# CW308T_EMF32TG11.net
KiCad netlist of a schematic drawn in Altium Designer
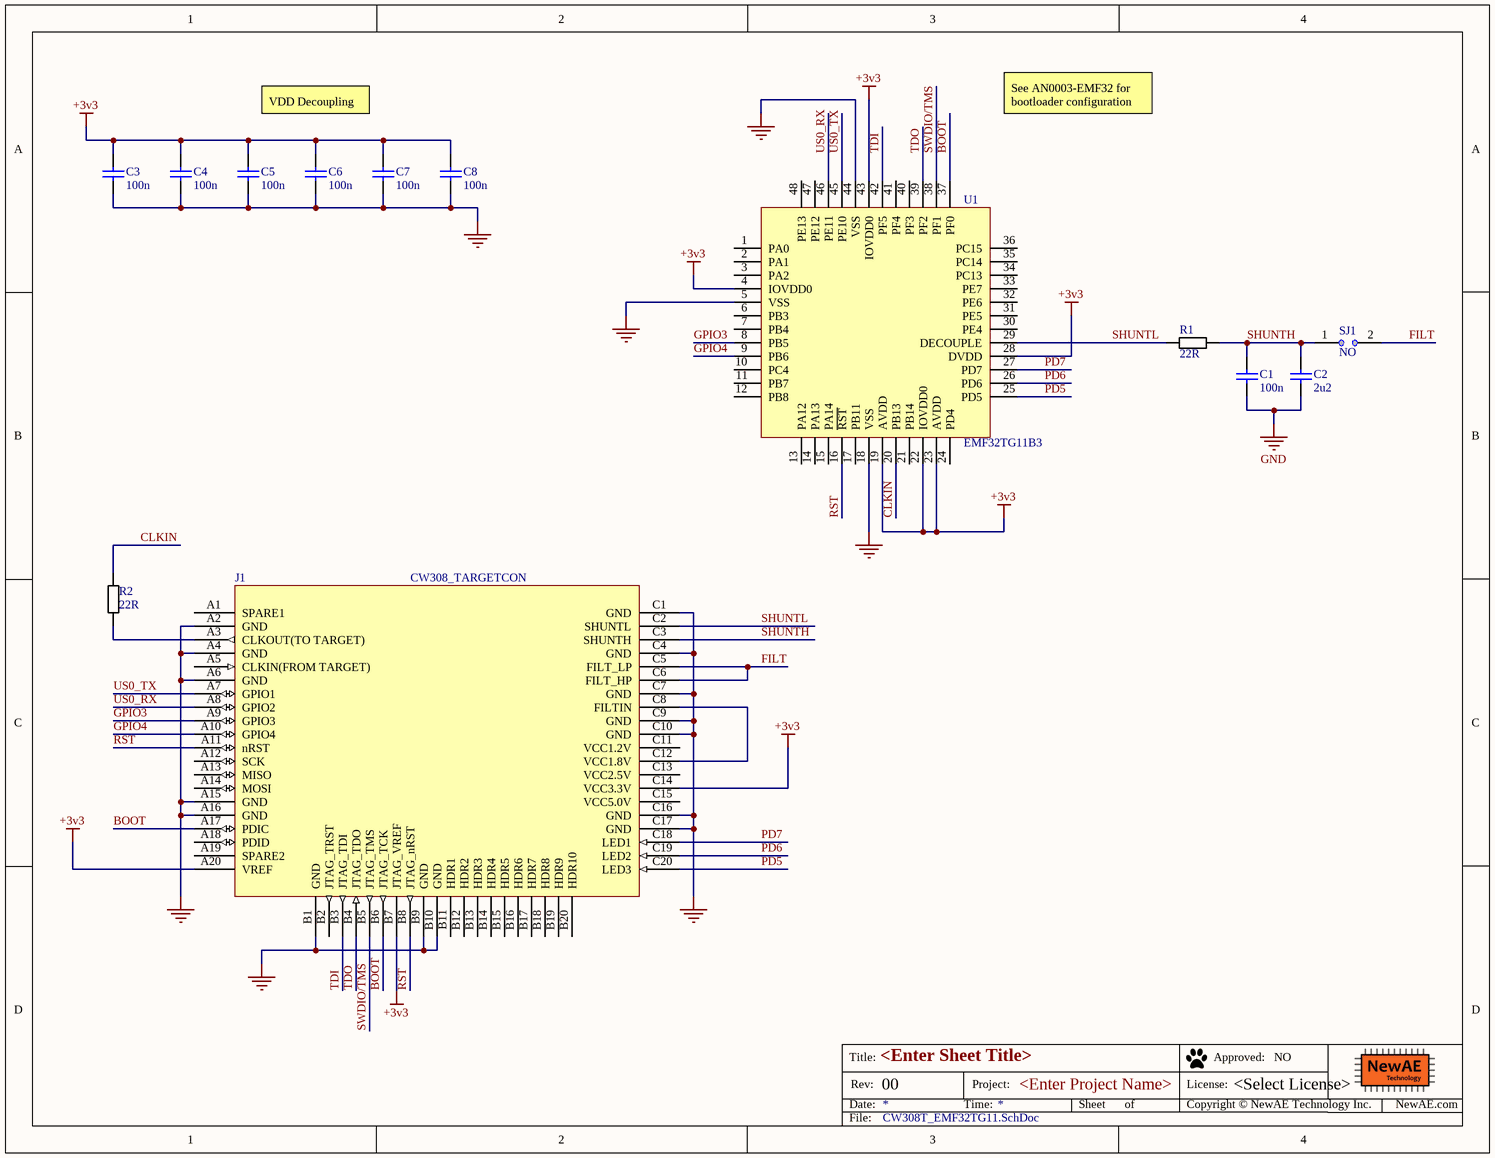
[diagram p0: CW308T_EMF32TG11.SchDoc]

(export (version "E")
  (design (tool "Eeschema 10.0.6"))
  (components
    (comp (ref "C1")
      (value "100n")
      (footprint "CAPC0603_M")
      (description "100n, 0603")
      (fields (field (name "PART NUMBER") "CCHIP-100n-0603"))
      (libsource (lib "NewAE_AltiumLib") (part "CAP"))
    )
    (comp (ref "C2")
      (value "2u2")
      (footprint "CAPC0603_M")
      (description "2u2, 0603")
      (fields (field (name "PART NUMBER") "CCHIP-2u2-0603"))
      (libsource (lib "NewAE_AltiumLib") (part "CAP"))
    )
    (comp (ref "C3")
      (value "100n")
      (footprint "CAPC0603_M")
      (description "100n, 0603")
      (fields (field (name "PART NUMBER") "CCHIP-100n-0603"))
      (libsource (lib "NewAE_AltiumLib") (part "CAP"))
    )
    (comp (ref "C4")
      (value "100n")
      (footprint "CAPC0603_M")
      (description "100n, 0603")
      (fields (field (name "PART NUMBER") "CCHIP-100n-0603"))
      (libsource (lib "NewAE_AltiumLib") (part "CAP"))
    )
    (comp (ref "C5")
      (value "100n")
      (footprint "CAPC0603_M")
      (description "100n, 0603")
      (fields (field (name "PART NUMBER") "CCHIP-100n-0603"))
      (libsource (lib "NewAE_AltiumLib") (part "CAP"))
    )
    (comp (ref "C6")
      (value "100n")
      (footprint "CAPC0603_M")
      (description "100n, 0603")
      (fields (field (name "PART NUMBER") "CCHIP-100n-0603"))
      (libsource (lib "NewAE_AltiumLib") (part "CAP"))
    )
    (comp (ref "C7")
      (value "100n")
      (footprint "CAPC0603_M")
      (description "100n, 0603")
      (fields (field (name "PART NUMBER") "CCHIP-100n-0603"))
      (libsource (lib "NewAE_AltiumLib") (part "CAP"))
    )
    (comp (ref "C8")
      (value "100n")
      (footprint "CAPC0603_M")
      (description "100n, 0603")
      (fields (field (name "PART NUMBER") "CCHIP-100n-0603"))
      (libsource (lib "NewAE_AltiumLib") (part "CAP"))
    )
    (comp (ref "J1")
      (value "CW308_TARGETCON")
      (footprint "CW308_TBOARD_CONN")
      (description "CW308 \"Standard\" Target Board Connector")
      (fields (field (name "PART NUMBER") "CW308_TBOARD"))
      (libsource (lib "NewAE_AltiumLib") (part "CW308_TBOARD"))
    )
    (comp (ref "R1")
      (value "22R")
      (footprint "RESC1608X55N")
      (description "22R res, 0603, 1%, 1/10W")
      (fields (field (name "PART NUMBER") "RCHIP-22R-0603") (field (name "TOLERANCE") "1%"))
      (libsource (lib "") (part "RES-EU_1"))
    )
    (comp (ref "R2")
      (value "22R")
      (footprint "RESC1608X55N")
      (description "22R res, 0603, 1%, 1/10W")
      (fields (field (name "PART NUMBER") "RCHIP-22R-0603") (field (name "TOLERANCE") "1%"))
      (libsource (lib "NewAE_AltiumLib") (part "RES-EU"))
    )
    (comp (ref "SJ1")
      (value "NO")
      (footprint "SJ_2S_NO")
      (description "Solder Jumper, NO")
      (fields (field (name "PART NUMBER") "SJ_2S_NO"))
      (libsource (lib "NewAE_AltiumLib") (part "SJ_2S_NO"))
    )
    (comp (ref "U1")
      (value "EMF32TG11B3")
      (footprint "TQFP48-P900X900X120")
      (description "MCU EMF32 Tiny Gecko 11 64kB 32kB 37 GPIO")
      (libsource (lib "NewAE_AltiumLib") (part "EMF32TG11B3"))
    )
  )
  (nets
    (net (code "1") (name "+3v3") (class "Default")
      (node (ref "C3") (pin "1") (pinfunction "1_1") (pintype "passive"))
      (node (ref "C4") (pin "1") (pinfunction "1_1") (pintype "passive"))
      (node (ref "C5") (pin "1") (pinfunction "1_1") (pintype "passive"))
      (node (ref "C6") (pin "1") (pinfunction "1_1") (pintype "passive"))
      (node (ref "C7") (pin "1") (pinfunction "1_1") (pintype "passive"))
      (node (ref "C8") (pin "1") (pinfunction "1_1") (pintype "passive"))
      (node (ref "J1") (pin "A20") (pinfunction "VREF_A20") (pintype "tri_state"))
      (node (ref "J1") (pin "B7") (pinfunction "JTAG_VREF_B7") (pintype "tri_state"))
      (node (ref "J1") (pin "C14") (pinfunction "VCC3.3V_C14") (pintype "power_in"))
      (node (ref "U1") (pin "19") (pinfunction "AVDD_19") (pintype "passive"))
      (node (ref "U1") (pin "22") (pinfunction "IOVDD0_22") (pintype "passive"))
      (node (ref "U1") (pin "23") (pinfunction "AVDD_23") (pintype "passive"))
      (node (ref "U1") (pin "28") (pinfunction "DVDD_28") (pintype "passive"))
      (node (ref "U1") (pin "4") (pinfunction "IOVDD0_4") (pintype "passive"))
      (node (ref "U1") (pin "43") (pinfunction "IOVDD0_43") (pintype "passive"))
    )
    (net (code "2") (name "/BOOT") (class "Default")
      (node (ref "J1") (pin "A17") (pinfunction "PDIC_A17") (pintype "bidirectional"))
      (node (ref "J1") (pin "B6") (pinfunction "JTAG_TCK_B6") (pintype "output"))
      (node (ref "U1") (pin "37") (pinfunction "PF0_37") (pintype "passive"))
    )
    (net (code "3") (name "/CLKIN") (class "Default")
      (node (ref "R2") (pin "1") (pinfunction "1_1") (pintype "passive"))
      (node (ref "U1") (pin "20") (pinfunction "PB13_20") (pintype "passive"))
    )
    (net (code "4") (name "/FILT") (class "Default")
      (node (ref "J1") (pin "C5") (pinfunction "FILT_LP_C5") (pintype "passive"))
      (node (ref "J1") (pin "C6") (pinfunction "FILT_HP_C6") (pintype "passive"))
      (node (ref "SJ1") (pin "2") (pinfunction "2_2") (pintype "passive"))
    )
    (net (code "5") (name "/GPIO3") (class "Default")
      (node (ref "J1") (pin "A9") (pinfunction "GPIO3_A9") (pintype "bidirectional"))
      (node (ref "U1") (pin "8") (pinfunction "PB5_8") (pintype "passive"))
    )
    (net (code "6") (name "/GPIO4") (class "Default")
      (node (ref "J1") (pin "A10") (pinfunction "GPIO4_A10") (pintype "bidirectional"))
      (node (ref "U1") (pin "9") (pinfunction "PB6_9") (pintype "passive"))
    )
    (net (code "7") (name "/PD5") (class "Default")
      (node (ref "J1") (pin "C20") (pinfunction "LED3_C20") (pintype "input"))
      (node (ref "U1") (pin "25") (pinfunction "PD5_25") (pintype "passive"))
    )
    (net (code "8") (name "/PD6") (class "Default")
      (node (ref "J1") (pin "C19") (pinfunction "LED2_C19") (pintype "input"))
      (node (ref "U1") (pin "26") (pinfunction "PD6_26") (pintype "passive"))
    )
    (net (code "9") (name "/PD7") (class "Default")
      (node (ref "J1") (pin "C18") (pinfunction "LED1_C18") (pintype "input"))
      (node (ref "U1") (pin "27") (pinfunction "PD7_27") (pintype "passive"))
    )
    (net (code "10") (name "/RST") (class "Default")
      (node (ref "J1") (pin "A11") (pinfunction "nRST_A11") (pintype "bidirectional"))
      (node (ref "J1") (pin "B8") (pinfunction "JTAG_nRST_B8") (pintype "output"))
      (node (ref "U1") (pin "16") (pinfunction "~{RST}_16") (pintype "passive"))
    )
    (net (code "11") (name "/SHUNTH") (class "Default")
      (node (ref "C1") (pin "1") (pinfunction "1_1") (pintype "passive"))
      (node (ref "C2") (pin "1") (pinfunction "1_1") (pintype "passive"))
      (node (ref "J1") (pin "C3") (pinfunction "SHUNTH_C3") (pintype "passive"))
      (node (ref "R1") (pin "2") (pinfunction "2_2") (pintype "passive"))
      (node (ref "SJ1") (pin "1") (pinfunction "1_1") (pintype "passive"))
    )
    (net (code "12") (name "/SHUNTL") (class "Default")
      (node (ref "J1") (pin "C2") (pinfunction "SHUNTL_C2") (pintype "passive"))
      (node (ref "R1") (pin "1") (pinfunction "1_1") (pintype "passive"))
      (node (ref "U1") (pin "29") (pinfunction "DECOUPLE_29") (pintype "passive"))
    )
    (net (code "13") (name "/SWDIO{slash}TMS") (class "Default")
      (node (ref "J1") (pin "B5") (pinfunction "JTAG_TMS_B5") (pintype "output"))
      (node (ref "U1") (pin "38") (pinfunction "PF1_38") (pintype "passive"))
    )
    (net (code "14") (name "/TDI") (class "Default")
      (node (ref "J1") (pin "B3") (pinfunction "JTAG_TDI_B3") (pintype "output"))
      (node (ref "U1") (pin "42") (pinfunction "PF5_42") (pintype "passive"))
    )
    (net (code "15") (name "/TDO") (class "Default")
      (node (ref "J1") (pin "B4") (pinfunction "JTAG_TDO_B4") (pintype "input"))
      (node (ref "U1") (pin "39") (pinfunction "PF2_39") (pintype "passive"))
    )
    (net (code "16") (name "/US0_RX") (class "Default")
      (node (ref "J1") (pin "A8") (pinfunction "GPIO2_A8") (pintype "bidirectional"))
      (node (ref "U1") (pin "46") (pinfunction "PE11_46") (pintype "passive"))
    )
    (net (code "17") (name "/US0_TX") (class "Default")
      (node (ref "J1") (pin "A7") (pinfunction "GPIO1_A7") (pintype "bidirectional"))
      (node (ref "U1") (pin "45") (pinfunction "PE10_45") (pintype "passive"))
    )
    (net (code "18") (name "GND") (class "Default")
      (node (ref "C1") (pin "2") (pinfunction "2_2") (pintype "passive"))
      (node (ref "C2") (pin "2") (pinfunction "2_2") (pintype "passive"))
      (node (ref "C3") (pin "2") (pinfunction "2_2") (pintype "passive"))
      (node (ref "C4") (pin "2") (pinfunction "2_2") (pintype "passive"))
      (node (ref "C5") (pin "2") (pinfunction "2_2") (pintype "passive"))
      (node (ref "C6") (pin "2") (pinfunction "2_2") (pintype "passive"))
      (node (ref "C7") (pin "2") (pinfunction "2_2") (pintype "passive"))
      (node (ref "C8") (pin "2") (pinfunction "2_2") (pintype "passive"))
      (node (ref "J1") (pin "A15") (pinfunction "GND_A15") (pintype "passive"))
      (node (ref "J1") (pin "A16") (pinfunction "GND_A16") (pintype "passive"))
      (node (ref "J1") (pin "A2") (pinfunction "GND_A2") (pintype "passive"))
      (node (ref "J1") (pin "A4") (pinfunction "GND_A4") (pintype "passive"))
      (node (ref "J1") (pin "A6") (pinfunction "GND_A6") (pintype "power_in"))
      (node (ref "J1") (pin "B1") (pinfunction "GND_B1") (pintype "passive"))
      (node (ref "J1") (pin "B10") (pinfunction "GND_B10") (pintype "passive"))
      (node (ref "J1") (pin "B9") (pinfunction "GND_B9") (pintype "passive"))
      (node (ref "J1") (pin "C1") (pinfunction "GND_C1") (pintype "power_in"))
      (node (ref "J1") (pin "C10") (pinfunction "GND_C10") (pintype "power_in"))
      (node (ref "J1") (pin "C16") (pinfunction "GND_C16") (pintype "power_in"))
      (node (ref "J1") (pin "C17") (pinfunction "GND_C17") (pintype "power_in"))
      (node (ref "J1") (pin "C4") (pinfunction "GND_C4") (pintype "power_in"))
      (node (ref "J1") (pin "C7") (pinfunction "GND_C7") (pintype "power_in"))
      (node (ref "J1") (pin "C9") (pinfunction "GND_C9") (pintype "power_in"))
      (node (ref "U1") (pin "18") (pinfunction "VSS_18") (pintype "passive"))
      (node (ref "U1") (pin "44") (pinfunction "VSS_44") (pintype "passive"))
      (node (ref "U1") (pin "5") (pinfunction "VSS_5") (pintype "passive"))
    )
    (net (code "19") (name "Net-(J1-CLKOUT(TO_TARGET))") (class "Default")
      (node (ref "J1") (pin "A3") (pinfunction "CLKOUT(TO_TARGET)_A3") (pintype "output"))
      (node (ref "R2") (pin "2") (pinfunction "2_2") (pintype "passive"))
    )
    (net (code "20") (name "Net-(J1-FILTIN)") (class "Default")
      (node (ref "J1") (pin "C12") (pinfunction "VCC1.8V_C12") (pintype "power_in"))
      (node (ref "J1") (pin "C8") (pinfunction "FILTIN_C8") (pintype "passive"))
    )
    (net (code "21") (name "unconnected-(J1-CLKIN(FROM_TARGET)-PadA5)") (class "Default")
      (node (ref "J1") (pin "A5") (pinfunction "CLKIN(FROM_TARGET)_A5") (pintype "input"))
    )
    (net (code "22") (name "unconnected-(J1-HDR1-PadB11)") (class "Default")
      (node (ref "J1") (pin "B11") (pinfunction "HDR1_B11") (pintype "passive"))
    )
    (net (code "23") (name "unconnected-(J1-HDR2-PadB12)") (class "Default")
      (node (ref "J1") (pin "B12") (pinfunction "HDR2_B12") (pintype "passive"))
    )
    (net (code "24") (name "unconnected-(J1-HDR3-PadB13)") (class "Default")
      (node (ref "J1") (pin "B13") (pinfunction "HDR3_B13") (pintype "passive"))
    )
    (net (code "25") (name "unconnected-(J1-HDR4-PadB14)") (class "Default")
      (node (ref "J1") (pin "B14") (pinfunction "HDR4_B14") (pintype "passive"))
    )
    (net (code "26") (name "unconnected-(J1-HDR5-PadB15)") (class "Default")
      (node (ref "J1") (pin "B15") (pinfunction "HDR5_B15") (pintype "passive"))
    )
    (net (code "27") (name "unconnected-(J1-HDR6-PadB16)") (class "Default")
      (node (ref "J1") (pin "B16") (pinfunction "HDR6_B16") (pintype "passive"))
    )
    (net (code "28") (name "unconnected-(J1-HDR7-PadB17)") (class "Default")
      (node (ref "J1") (pin "B17") (pinfunction "HDR7_B17") (pintype "passive"))
    )
    (net (code "29") (name "unconnected-(J1-HDR8-PadB18)") (class "Default")
      (node (ref "J1") (pin "B18") (pinfunction "HDR8_B18") (pintype "passive"))
    )
    (net (code "30") (name "unconnected-(J1-HDR9-PadB19)") (class "Default")
      (node (ref "J1") (pin "B19") (pinfunction "HDR9_B19") (pintype "passive"))
    )
    (net (code "31") (name "unconnected-(J1-HDR10-PadB20)") (class "Default")
      (node (ref "J1") (pin "B20") (pinfunction "HDR10_B20") (pintype "passive"))
    )
    (net (code "32") (name "unconnected-(J1-JTAG_TRST-PadB2)") (class "Default")
      (node (ref "J1") (pin "B2") (pinfunction "JTAG_TRST_B2") (pintype "output"))
    )
    (net (code "33") (name "unconnected-(J1-MISO-PadA13)") (class "Default")
      (node (ref "J1") (pin "A13") (pinfunction "MISO_A13") (pintype "bidirectional"))
    )
    (net (code "34") (name "unconnected-(J1-MOSI-PadA14)") (class "Default")
      (node (ref "J1") (pin "A14") (pinfunction "MOSI_A14") (pintype "bidirectional"))
    )
    (net (code "35") (name "unconnected-(J1-PDID-PadA18)") (class "Default")
      (node (ref "J1") (pin "A18") (pinfunction "PDID_A18") (pintype "bidirectional"))
    )
    (net (code "36") (name "unconnected-(J1-SCK-PadA12)") (class "Default")
      (node (ref "J1") (pin "A12") (pinfunction "SCK_A12") (pintype "bidirectional"))
    )
    (net (code "37") (name "unconnected-(J1-SPARE1-PadA1)") (class "Default")
      (node (ref "J1") (pin "A1") (pinfunction "SPARE1_A1") (pintype "passive"))
    )
    (net (code "38") (name "unconnected-(J1-SPARE2-PadA19)") (class "Default")
      (node (ref "J1") (pin "A19") (pinfunction "SPARE2_A19") (pintype "passive"))
    )
    (net (code "39") (name "unconnected-(J1-VCC1.2V-PadC11)") (class "Default")
      (node (ref "J1") (pin "C11") (pinfunction "VCC1.2V_C11") (pintype "power_in"))
    )
    (net (code "40") (name "unconnected-(J1-VCC2.5V-PadC13)") (class "Default")
      (node (ref "J1") (pin "C13") (pinfunction "VCC2.5V_C13") (pintype "power_in"))
    )
    (net (code "41") (name "unconnected-(J1-VCC5.0V-PadC15)") (class "Default")
      (node (ref "J1") (pin "C15") (pinfunction "VCC5.0V_C15") (pintype "power_in"))
    )
    (net (code "42") (name "unconnected-(U1-PA0-Pad1)") (class "Default")
      (node (ref "U1") (pin "1") (pinfunction "PA0_1") (pintype "passive"))
    )
    (net (code "43") (name "unconnected-(U1-PA1-Pad2)") (class "Default")
      (node (ref "U1") (pin "2") (pinfunction "PA1_2") (pintype "passive"))
    )
    (net (code "44") (name "unconnected-(U1-PA2-Pad3)") (class "Default")
      (node (ref "U1") (pin "3") (pinfunction "PA2_3") (pintype "passive"))
    )
    (net (code "45") (name "unconnected-(U1-PA12-Pad13)") (class "Default")
      (node (ref "U1") (pin "13") (pinfunction "PA12_13") (pintype "passive"))
    )
    (net (code "46") (name "unconnected-(U1-PA13-Pad14)") (class "Default")
      (node (ref "U1") (pin "14") (pinfunction "PA13_14") (pintype "passive"))
    )
    (net (code "47") (name "unconnected-(U1-PA14-Pad15)") (class "Default")
      (node (ref "U1") (pin "15") (pinfunction "PA14_15") (pintype "passive"))
    )
    (net (code "48") (name "unconnected-(U1-PB3-Pad6)") (class "Default")
      (node (ref "U1") (pin "6") (pinfunction "PB3_6") (pintype "passive"))
    )
    (net (code "49") (name "unconnected-(U1-PB4-Pad7)") (class "Default")
      (node (ref "U1") (pin "7") (pinfunction "PB4_7") (pintype "passive"))
    )
    (net (code "50") (name "unconnected-(U1-PB7-Pad11)") (class "Default")
      (node (ref "U1") (pin "11") (pinfunction "PB7_11") (pintype "passive"))
    )
    (net (code "51") (name "unconnected-(U1-PB8-Pad12)") (class "Default")
      (node (ref "U1") (pin "12") (pinfunction "PB8_12") (pintype "passive"))
    )
    (net (code "52") (name "unconnected-(U1-PB11-Pad17)") (class "Default")
      (node (ref "U1") (pin "17") (pinfunction "PB11_17") (pintype "passive"))
    )
    (net (code "53") (name "unconnected-(U1-PB14-Pad21)") (class "Default")
      (node (ref "U1") (pin "21") (pinfunction "PB14_21") (pintype "passive"))
    )
    (net (code "54") (name "unconnected-(U1-PC4-Pad10)") (class "Default")
      (node (ref "U1") (pin "10") (pinfunction "PC4_10") (pintype "passive"))
    )
    (net (code "55") (name "unconnected-(U1-PC13-Pad34)") (class "Default")
      (node (ref "U1") (pin "34") (pinfunction "PC13_34") (pintype "passive"))
    )
    (net (code "56") (name "unconnected-(U1-PC14-Pad35)") (class "Default")
      (node (ref "U1") (pin "35") (pinfunction "PC14_35") (pintype "passive"))
    )
    (net (code "57") (name "unconnected-(U1-PC15-Pad36)") (class "Default")
      (node (ref "U1") (pin "36") (pinfunction "PC15_36") (pintype "passive"))
    )
    (net (code "58") (name "unconnected-(U1-PD4-Pad24)") (class "Default")
      (node (ref "U1") (pin "24") (pinfunction "PD4_24") (pintype "passive"))
    )
    (net (code "59") (name "unconnected-(U1-PE4-Pad30)") (class "Default")
      (node (ref "U1") (pin "30") (pinfunction "PE4_30") (pintype "passive"))
    )
    (net (code "60") (name "unconnected-(U1-PE5-Pad31)") (class "Default")
      (node (ref "U1") (pin "31") (pinfunction "PE5_31") (pintype "passive"))
    )
    (net (code "61") (name "unconnected-(U1-PE6-Pad32)") (class "Default")
      (node (ref "U1") (pin "32") (pinfunction "PE6_32") (pintype "passive"))
    )
    (net (code "62") (name "unconnected-(U1-PE7-Pad33)") (class "Default")
      (node (ref "U1") (pin "33") (pinfunction "PE7_33") (pintype "passive"))
    )
    (net (code "63") (name "unconnected-(U1-PE12-Pad47)") (class "Default")
      (node (ref "U1") (pin "47") (pinfunction "PE12_47") (pintype "passive"))
    )
    (net (code "64") (name "unconnected-(U1-PE13-Pad48)") (class "Default")
      (node (ref "U1") (pin "48") (pinfunction "PE13_48") (pintype "passive"))
    )
    (net (code "65") (name "unconnected-(U1-PF3-Pad40)") (class "Default")
      (node (ref "U1") (pin "40") (pinfunction "PF3_40") (pintype "passive"))
    )
    (net (code "66") (name "unconnected-(U1-PF4-Pad41)") (class "Default")
      (node (ref "U1") (pin "41") (pinfunction "PF4_41") (pintype "passive"))
    )
  )
)
